# EEPROM.net
KiCad netlist of a schematic drawn in Altium Designer
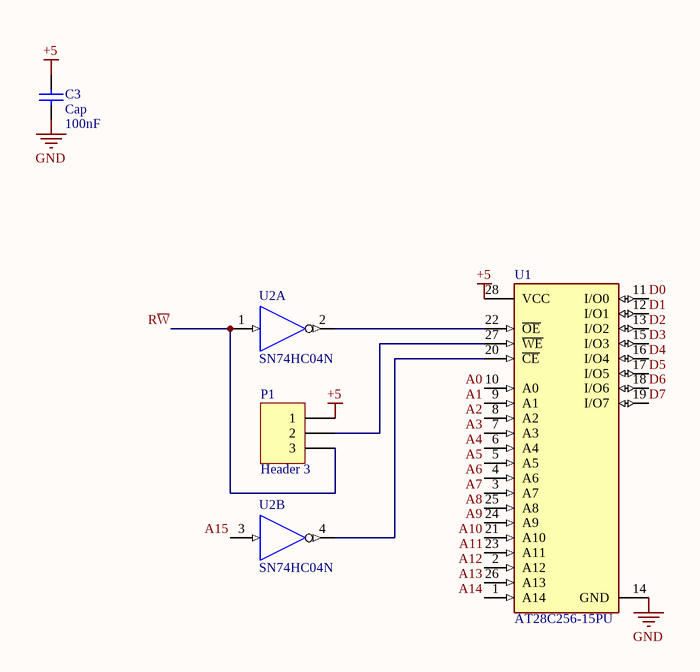
[diagram p0: EEPROM.SchDoc]

(export (version "E")
  (design (tool "Eeschema 10.0.6"))
  (components
    (comp (ref "C3")
      (value "Cap")
      (footprint "Ceramic Capacitor")
      (description "Capacitor")
      (fields (field (name "ALTIUM_VALUE") "100nF") (field (name "PUBLISHER") "Altium Limited"))
      (libsource (lib "Miscellaneous Devices") (part "Cap"))
    )
    (comp (ref "P1")
      (value "Header 3")
      (footprint "HDR1X3")
      (description "Header, 3-Pin")
      (fields (field (name "PUBLISHER") "Altium Limited"))
      (libsource (lib "Miscellaneous Connectors") (part "Header 3"))
    )
    (comp (ref "U1")
      (value "AT28C256-15PU")
      (footprint "FP-28P6-MFG")
      (description "IC EEPROM 256K PARALLEL 28DIP")
      (fields
        (field (name "MANUFACTURER") "Microchip")
        (field (name "OCTOPART") "https://octopart.com/at28c256-15pu-microchip-77758240")
      )
      (libsource (lib "Altium Content Vault") (part "df06beef5d7b4d1cd730806cb3934f7"))
    )
    (comp (ref "U2")
      (value "SN74HC04N")
      (footprint "N0014A")
      (description "Hex Inverters, N0014A, TUBE")
      (fields
        (field (name "MANUFACTURER") "Texas Instruments")
        (field (name "GENERIC PART NUMBER") "SN74HC04")
      )
      (libsource (lib "Altium Content Vault") (part "TI-CD_SNX4XXXXXX4X_19A-14"))
    )
  )
  (nets
    (net (code "1") (name "+5") (class "Default")
      (node (ref "C3") (pin "1") (pinfunction "1_1") (pintype "passive"))
      (node (ref "P1") (pin "1") (pinfunction "1_1") (pintype "passive"))
      (node (ref "U1") (pin "28") (pinfunction "VCC_28") (pintype "power_in"))
    )
    (net (code "2") (name "/A0") (class "Default")
      (node (ref "U1") (pin "10") (pinfunction "A0_10") (pintype "input"))
    )
    (net (code "3") (name "/A1") (class "Default")
      (node (ref "U1") (pin "9") (pinfunction "A1_9") (pintype "input"))
    )
    (net (code "4") (name "/A2") (class "Default")
      (node (ref "U1") (pin "8") (pinfunction "A2_8") (pintype "input"))
    )
    (net (code "5") (name "/A3") (class "Default")
      (node (ref "U1") (pin "7") (pinfunction "A3_7") (pintype "input"))
    )
    (net (code "6") (name "/A4") (class "Default")
      (node (ref "U1") (pin "6") (pinfunction "A4_6") (pintype "input"))
    )
    (net (code "7") (name "/A5") (class "Default")
      (node (ref "U1") (pin "5") (pinfunction "A5_5") (pintype "input"))
    )
    (net (code "8") (name "/A6") (class "Default")
      (node (ref "U1") (pin "4") (pinfunction "A6_4") (pintype "input"))
    )
    (net (code "9") (name "/A7") (class "Default")
      (node (ref "U1") (pin "3") (pinfunction "A7_3") (pintype "input"))
    )
    (net (code "10") (name "/A8") (class "Default")
      (node (ref "U1") (pin "25") (pinfunction "A8_25") (pintype "input"))
    )
    (net (code "11") (name "/A9") (class "Default")
      (node (ref "U1") (pin "24") (pinfunction "A9_24") (pintype "input"))
    )
    (net (code "12") (name "/A10") (class "Default")
      (node (ref "U1") (pin "21") (pinfunction "A10_21") (pintype "input"))
    )
    (net (code "13") (name "/A11") (class "Default")
      (node (ref "U1") (pin "23") (pinfunction "A11_23") (pintype "input"))
    )
    (net (code "14") (name "/A12") (class "Default")
      (node (ref "U1") (pin "2") (pinfunction "A12_2") (pintype "input"))
    )
    (net (code "15") (name "/A13") (class "Default")
      (node (ref "U1") (pin "26") (pinfunction "A13_26") (pintype "input"))
    )
    (net (code "16") (name "/A14") (class "Default")
      (node (ref "U1") (pin "1") (pinfunction "A14_1") (pintype "input"))
    )
    (net (code "17") (name "/A15") (class "Default")
      (node (ref "U2") (pin "3") (pinfunction "2A_3") (pintype "input"))
    )
    (net (code "18") (name "/D0") (class "Default")
      (node (ref "U1") (pin "11") (pinfunction "I/O0_11") (pintype "bidirectional"))
    )
    (net (code "19") (name "/D1") (class "Default")
      (node (ref "U1") (pin "12") (pinfunction "I/O1_12") (pintype "bidirectional"))
    )
    (net (code "20") (name "/D2") (class "Default")
      (node (ref "U1") (pin "13") (pinfunction "I/O2_13") (pintype "bidirectional"))
    )
    (net (code "21") (name "/D3") (class "Default")
      (node (ref "U1") (pin "15") (pinfunction "I/O3_15") (pintype "bidirectional"))
    )
    (net (code "22") (name "/D4") (class "Default")
      (node (ref "U1") (pin "16") (pinfunction "I/O4_16") (pintype "bidirectional"))
    )
    (net (code "23") (name "/D5") (class "Default")
      (node (ref "U1") (pin "17") (pinfunction "I/O5_17") (pintype "bidirectional"))
    )
    (net (code "24") (name "/D6") (class "Default")
      (node (ref "U1") (pin "18") (pinfunction "I/O6_18") (pintype "bidirectional"))
    )
    (net (code "25") (name "/D7") (class "Default")
      (node (ref "U1") (pin "19") (pinfunction "I/O7_19") (pintype "bidirectional"))
    )
    (net (code "26") (name "/R~{W}") (class "Default")
      (node (ref "P1") (pin "3") (pinfunction "3_3") (pintype "passive"))
      (node (ref "U2") (pin "1") (pinfunction "1A_1") (pintype "input"))
    )
    (net (code "27") (name "GND") (class "Default")
      (node (ref "C3") (pin "2") (pinfunction "2_2") (pintype "passive"))
      (node (ref "U1") (pin "14") (pinfunction "GND_14") (pintype "power_in"))
    )
    (net (code "28") (name "Net-(U1-~{CE})") (class "Default")
      (node (ref "U1") (pin "20") (pinfunction "~{CE}_20") (pintype "input"))
      (node (ref "U2") (pin "4") (pinfunction "~{2Y}_4") (pintype "output"))
    )
    (net (code "29") (name "Net-(U1-~{OE})") (class "Default")
      (node (ref "U1") (pin "22") (pinfunction "~{OE}_22") (pintype "input"))
      (node (ref "U2") (pin "2") (pinfunction "~{1Y}_2") (pintype "output"))
    )
    (net (code "30") (name "Net-(U1-~{WE})") (class "Default")
      (node (ref "P1") (pin "2") (pinfunction "2_2") (pintype "passive"))
      (node (ref "U1") (pin "27") (pinfunction "~{WE}_27") (pintype "input"))
    )
  )
)
